# Netscale48HD_Antenna_Selector.net
KiCad netlist of a schematic drawn in Altium Designer
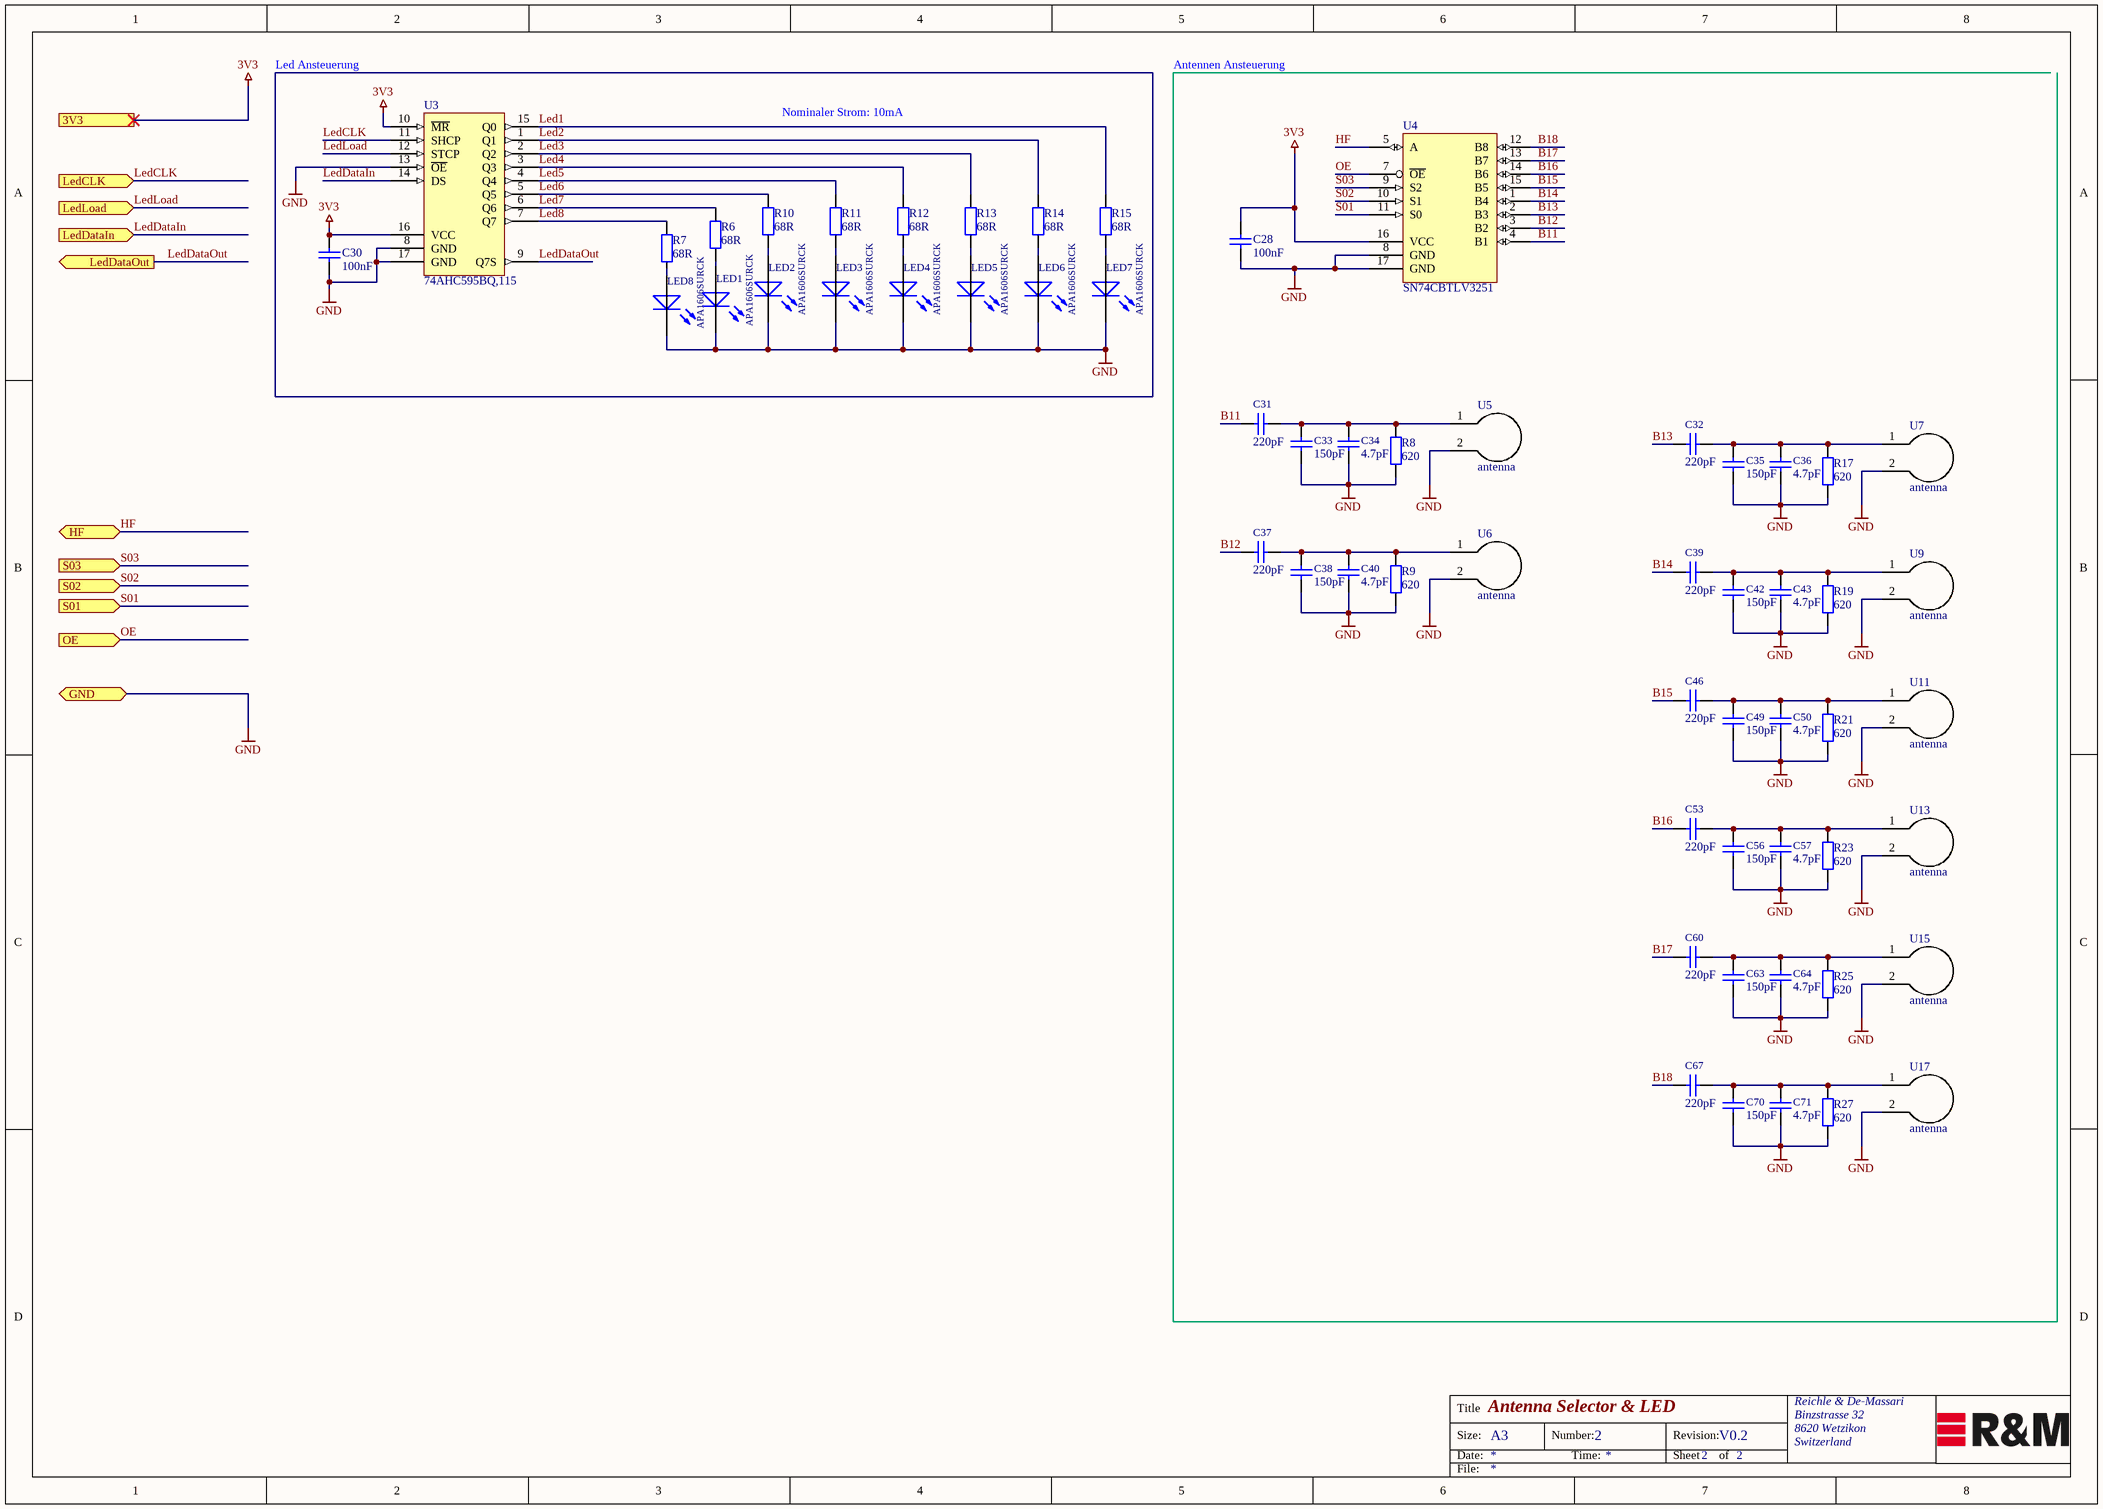
[diagram p0: Netscale48HD_Antenna_Selector.SchDoc]

(export (version "E")
  (design (tool "Eeschema 10.0.6"))
  (components
    (comp (ref "C28")
      (value "100nF")
      (footprint "CAPC1005X55N")
      (description "0.1µF ±10% 10V Ceramic Capacitor X5R 0402 (1005 Metric)")
      (fields (field (name "TOLERANCE") "Â±10%") (field (name "MANUFACTURER") "Taiyo Yuden"))
      (libsource (lib "altium-import") (part "root_1_CMP-1033-00660-1_"))
    )
    (comp (ref "C30")
      (value "100nF")
      (footprint "CAPC1005X55N")
      (description "0.1µF ±10% 10V Ceramic Capacitor X5R 0402 (1005 Metric)")
      (fields (field (name "TOLERANCE") "Â±10%") (field (name "MANUFACTURER") "Taiyo Yuden"))
      (libsource (lib "altium-import") (part "root_1_CMP-1033-00660-1_"))
    )
    (comp (ref "C31")
      (value "220pF")
      (footprint "CAPC1005X55N")
      (description "220pF ±1% 50V Ceramic Capacitor C0G, NP0 0402 (1005 Metric)")
      (fields
        (field (name "MANUFACTURER") "Murata Electronics")
        (field (name "Comment") "GCM1555C1H221FA16D")
      )
      (libsource (lib "NTB Vault") (part "706xx_R+M_InteliPhyII_KTI-00070-A.1"))
    )
    (comp (ref "C32")
      (value "220pF")
      (footprint "CAPC1005X55N")
      (description "220pF ±1% 50V Ceramic Capacitor C0G, NP0 0402 (1005 Metric)")
      (fields
        (field (name "MANUFACTURER") "Murata Electronics")
        (field (name "Comment") "GCM1555C1H221FA16D")
      )
      (libsource (lib "NTB Vault") (part "706xx_R+M_InteliPhyII_KTI-00070-A.1"))
    )
    (comp (ref "C33")
      (value "150pF")
      (footprint "CAPC1005X55N")
      (description "150pF ±1% 50V Ceramic Capacitor C0G, NP0 0402 (1005 Metric)")
      (fields
        (field (name "MANUFACTURER") "Murata Electronics North America")
        (field (name "Comment") "GRM1555C1H151FA01D")
      )
      (libsource (lib "NTB Vault") (part "706xx_R+M_InteliPhyII_KTI-00069-A.1"))
    )
    (comp (ref "C34")
      (value "4.7pF")
      (footprint "CAPC1005X55N")
      (description "4.7pF ±0.05pF 50V Ceramic Capacitor C0G, NP0 0402 (1005 Metric)")
      (fields
        (field (name "MANUFACTURER") "Murata Electronics North America")
        (field (name "Comment") "GJM1555C1H4R7WB01D")
      )
      (libsource (lib "NTB Vault") (part "706xx_R+M_InteliPhyII_KTI-00023-A.1"))
    )
    (comp (ref "C35")
      (value "150pF")
      (footprint "CAPC1005X55N")
      (description "150pF ±1% 50V Ceramic Capacitor C0G, NP0 0402 (1005 Metric)")
      (fields
        (field (name "MANUFACTURER") "Murata Electronics North America")
        (field (name "Comment") "GRM1555C1H151FA01D")
      )
      (libsource (lib "NTB Vault") (part "706xx_R+M_InteliPhyII_KTI-00069-A.1"))
    )
    (comp (ref "C36")
      (value "4.7pF")
      (footprint "CAPC1005X55N")
      (description "4.7pF ±0.05pF 50V Ceramic Capacitor C0G, NP0 0402 (1005 Metric)")
      (fields
        (field (name "MANUFACTURER") "Murata Electronics North America")
        (field (name "Comment") "GJM1555C1H4R7WB01D")
      )
      (libsource (lib "NTB Vault") (part "706xx_R+M_InteliPhyII_KTI-00023-A.1"))
    )
    (comp (ref "C37")
      (value "220pF")
      (footprint "CAPC1005X55N")
      (description "220pF ±1% 50V Ceramic Capacitor C0G, NP0 0402 (1005 Metric)")
      (fields
        (field (name "MANUFACTURER") "Murata Electronics")
        (field (name "Comment") "GCM1555C1H221FA16D")
      )
      (libsource (lib "NTB Vault") (part "706xx_R+M_InteliPhyII_KTI-00070-A.1"))
    )
    (comp (ref "C38")
      (value "150pF")
      (footprint "CAPC1005X55N")
      (description "150pF ±1% 50V Ceramic Capacitor C0G, NP0 0402 (1005 Metric)")
      (fields
        (field (name "MANUFACTURER") "Murata Electronics North America")
        (field (name "Comment") "GRM1555C1H151FA01D")
      )
      (libsource (lib "NTB Vault") (part "706xx_R+M_InteliPhyII_KTI-00069-A.1"))
    )
    (comp (ref "C39")
      (value "220pF")
      (footprint "CAPC1005X55N")
      (description "220pF ±1% 50V Ceramic Capacitor C0G, NP0 0402 (1005 Metric)")
      (fields
        (field (name "MANUFACTURER") "Murata Electronics")
        (field (name "Comment") "GCM1555C1H221FA16D")
      )
      (libsource (lib "NTB Vault") (part "706xx_R+M_InteliPhyII_KTI-00070-A.1"))
    )
    (comp (ref "C40")
      (value "4.7pF")
      (footprint "CAPC1005X55N")
      (description "4.7pF ±0.05pF 50V Ceramic Capacitor C0G, NP0 0402 (1005 Metric)")
      (fields
        (field (name "MANUFACTURER") "Murata Electronics North America")
        (field (name "Comment") "GJM1555C1H4R7WB01D")
      )
      (libsource (lib "NTB Vault") (part "706xx_R+M_InteliPhyII_KTI-00023-A.1"))
    )
    (comp (ref "C42")
      (value "150pF")
      (footprint "CAPC1005X55N")
      (description "150pF ±1% 50V Ceramic Capacitor C0G, NP0 0402 (1005 Metric)")
      (fields
        (field (name "MANUFACTURER") "Murata Electronics North America")
        (field (name "Comment") "GRM1555C1H151FA01D")
      )
      (libsource (lib "NTB Vault") (part "706xx_R+M_InteliPhyII_KTI-00069-A.1"))
    )
    (comp (ref "C43")
      (value "4.7pF")
      (footprint "CAPC1005X55N")
      (description "4.7pF ±0.05pF 50V Ceramic Capacitor C0G, NP0 0402 (1005 Metric)")
      (fields
        (field (name "MANUFACTURER") "Murata Electronics North America")
        (field (name "Comment") "GJM1555C1H4R7WB01D")
      )
      (libsource (lib "NTB Vault") (part "706xx_R+M_InteliPhyII_KTI-00023-A.1"))
    )
    (comp (ref "C46")
      (value "220pF")
      (footprint "CAPC1005X55N")
      (description "220pF ±1% 50V Ceramic Capacitor C0G, NP0 0402 (1005 Metric)")
      (fields
        (field (name "MANUFACTURER") "Murata Electronics")
        (field (name "Comment") "GCM1555C1H221FA16D")
      )
      (libsource (lib "NTB Vault") (part "706xx_R+M_InteliPhyII_KTI-00070-A.1"))
    )
    (comp (ref "C49")
      (value "150pF")
      (footprint "CAPC1005X55N")
      (description "150pF ±1% 50V Ceramic Capacitor C0G, NP0 0402 (1005 Metric)")
      (fields
        (field (name "MANUFACTURER") "Murata Electronics North America")
        (field (name "Comment") "GRM1555C1H151FA01D")
      )
      (libsource (lib "NTB Vault") (part "706xx_R+M_InteliPhyII_KTI-00069-A.1"))
    )
    (comp (ref "C50")
      (value "4.7pF")
      (footprint "CAPC1005X55N")
      (description "4.7pF ±0.05pF 50V Ceramic Capacitor C0G, NP0 0402 (1005 Metric)")
      (fields
        (field (name "MANUFACTURER") "Murata Electronics North America")
        (field (name "Comment") "GJM1555C1H4R7WB01D")
      )
      (libsource (lib "NTB Vault") (part "706xx_R+M_InteliPhyII_KTI-00023-A.1"))
    )
    (comp (ref "C53")
      (value "220pF")
      (footprint "CAPC1005X55N")
      (description "220pF ±1% 50V Ceramic Capacitor C0G, NP0 0402 (1005 Metric)")
      (fields
        (field (name "MANUFACTURER") "Murata Electronics")
        (field (name "Comment") "GCM1555C1H221FA16D")
      )
      (libsource (lib "NTB Vault") (part "706xx_R+M_InteliPhyII_KTI-00070-A.1"))
    )
    (comp (ref "C56")
      (value "150pF")
      (footprint "CAPC1005X55N")
      (description "150pF ±1% 50V Ceramic Capacitor C0G, NP0 0402 (1005 Metric)")
      (fields
        (field (name "MANUFACTURER") "Murata Electronics North America")
        (field (name "Comment") "GRM1555C1H151FA01D")
      )
      (libsource (lib "NTB Vault") (part "706xx_R+M_InteliPhyII_KTI-00069-A.1"))
    )
    (comp (ref "C57")
      (value "4.7pF")
      (footprint "CAPC1005X55N")
      (description "4.7pF ±0.05pF 50V Ceramic Capacitor C0G, NP0 0402 (1005 Metric)")
      (fields
        (field (name "MANUFACTURER") "Murata Electronics North America")
        (field (name "Comment") "GJM1555C1H4R7WB01D")
      )
      (libsource (lib "NTB Vault") (part "706xx_R+M_InteliPhyII_KTI-00023-A.1"))
    )
    (comp (ref "C60")
      (value "220pF")
      (footprint "CAPC1005X55N")
      (description "220pF ±1% 50V Ceramic Capacitor C0G, NP0 0402 (1005 Metric)")
      (fields
        (field (name "MANUFACTURER") "Murata Electronics")
        (field (name "Comment") "GCM1555C1H221FA16D")
      )
      (libsource (lib "NTB Vault") (part "706xx_R+M_InteliPhyII_KTI-00070-A.1"))
    )
    (comp (ref "C63")
      (value "150pF")
      (footprint "CAPC1005X55N")
      (description "150pF ±1% 50V Ceramic Capacitor C0G, NP0 0402 (1005 Metric)")
      (fields
        (field (name "MANUFACTURER") "Murata Electronics North America")
        (field (name "Comment") "GRM1555C1H151FA01D")
      )
      (libsource (lib "NTB Vault") (part "706xx_R+M_InteliPhyII_KTI-00069-A.1"))
    )
    (comp (ref "C64")
      (value "4.7pF")
      (footprint "CAPC1005X55N")
      (description "4.7pF ±0.05pF 50V Ceramic Capacitor C0G, NP0 0402 (1005 Metric)")
      (fields
        (field (name "MANUFACTURER") "Murata Electronics North America")
        (field (name "Comment") "GJM1555C1H4R7WB01D")
      )
      (libsource (lib "NTB Vault") (part "706xx_R+M_InteliPhyII_KTI-00023-A.1"))
    )
    (comp (ref "C67")
      (value "220pF")
      (footprint "CAPC1005X55N")
      (description "220pF ±1% 50V Ceramic Capacitor C0G, NP0 0402 (1005 Metric)")
      (fields
        (field (name "MANUFACTURER") "Murata Electronics")
        (field (name "Comment") "GCM1555C1H221FA16D")
      )
      (libsource (lib "NTB Vault") (part "706xx_R+M_InteliPhyII_KTI-00070-A.1"))
    )
    (comp (ref "C70")
      (value "150pF")
      (footprint "CAPC1005X55N")
      (description "150pF ±1% 50V Ceramic Capacitor C0G, NP0 0402 (1005 Metric)")
      (fields
        (field (name "MANUFACTURER") "Murata Electronics North America")
        (field (name "Comment") "GRM1555C1H151FA01D")
      )
      (libsource (lib "NTB Vault") (part "706xx_R+M_InteliPhyII_KTI-00069-A.1"))
    )
    (comp (ref "C71")
      (value "4.7pF")
      (footprint "CAPC1005X55N")
      (description "4.7pF ±0.05pF 50V Ceramic Capacitor C0G, NP0 0402 (1005 Metric)")
      (fields
        (field (name "MANUFACTURER") "Murata Electronics North America")
        (field (name "Comment") "GJM1555C1H4R7WB01D")
      )
      (libsource (lib "NTB Vault") (part "706xx_R+M_InteliPhyII_KTI-00023-A.1"))
    )
    (comp (ref "LED1")
      (value "APA1606SURCK")
      (footprint "Kingbright_SMD_2_RWH")
      (description "Red 630nm LED Indication - Discrete 1.95V 2-SMD, No Lead")
      (fields (field (name "MANUFACTURER") "Kingbright"))
      (libsource (lib "altium-import") (part "root_1_LED_K1_A2_"))
    )
    (comp (ref "LED2")
      (value "APA1606SURCK")
      (footprint "Kingbright_SMD_2_RWH")
      (description "Red 630nm LED Indication - Discrete 1.95V 2-SMD, No Lead")
      (fields (field (name "MANUFACTURER") "Kingbright"))
      (libsource (lib "altium-import") (part "root_1_LED_K1_A2_"))
    )
    (comp (ref "LED3")
      (value "APA1606SURCK")
      (footprint "Kingbright_SMD_2_RWH")
      (description "Red 630nm LED Indication - Discrete 1.95V 2-SMD, No Lead")
      (fields (field (name "MANUFACTURER") "Kingbright"))
      (libsource (lib "altium-import") (part "root_1_LED_K1_A2_"))
    )
    (comp (ref "LED4")
      (value "APA1606SURCK")
      (footprint "Kingbright_SMD_2_RWH")
      (description "Red 630nm LED Indication - Discrete 1.95V 2-SMD, No Lead")
      (fields (field (name "MANUFACTURER") "Kingbright"))
      (libsource (lib "altium-import") (part "root_1_LED_K1_A2_"))
    )
    (comp (ref "LED5")
      (value "APA1606SURCK")
      (footprint "Kingbright_SMD_2_RWH")
      (description "Red 630nm LED Indication - Discrete 1.95V 2-SMD, No Lead")
      (fields (field (name "MANUFACTURER") "Kingbright"))
      (libsource (lib "altium-import") (part "root_1_LED_K1_A2_"))
    )
    (comp (ref "LED6")
      (value "APA1606SURCK")
      (footprint "Kingbright_SMD_2_RWH")
      (description "Red 630nm LED Indication - Discrete 1.95V 2-SMD, No Lead")
      (fields (field (name "MANUFACTURER") "Kingbright"))
      (libsource (lib "altium-import") (part "root_1_LED_K1_A2_"))
    )
    (comp (ref "LED7")
      (value "APA1606SURCK")
      (footprint "Kingbright_SMD_2_RWH")
      (description "Red 630nm LED Indication - Discrete 1.95V 2-SMD, No Lead")
      (fields (field (name "MANUFACTURER") "Kingbright"))
      (libsource (lib "altium-import") (part "root_1_LED_K1_A2_"))
    )
    (comp (ref "LED8")
      (value "APA1606SURCK")
      (footprint "Kingbright_SMD_2_RWH")
      (description "Red 630nm LED Indication - Discrete 1.95V 2-SMD, No Lead")
      (fields (field (name "MANUFACTURER") "Kingbright"))
      (libsource (lib "altium-import") (part "root_1_LED_K1_A2_"))
    )
    (comp (ref "R6")
      (value "68R")
      (footprint "RESC1005X40N")
      (description "68 Ohms ±1% 0.125W, 1/8W Chip Resistor 0402 (1005 Metric) Pulse Withstanding Thick Film")
      (fields
        (field (name "MANUFACTURER") "TE Connectivity Passive Product")
        (field (name "Comment") "CRGP0402F68R")
      )
      (libsource (lib "") (part "PassResBas0201-00055-A.2_1"))
    )
    (comp (ref "R7")
      (value "68R")
      (footprint "RESC1005X40N")
      (description "68 Ohms ±1% 0.125W, 1/8W Chip Resistor 0402 (1005 Metric) Pulse Withstanding Thick Film")
      (fields
        (field (name "MANUFACTURER") "TE Connectivity Passive Product")
        (field (name "Comment") "CRGP0402F68R")
      )
      (libsource (lib "") (part "PassResBas0201-00055-A.2_1"))
    )
    (comp (ref "R8")
      (value "620")
      (footprint "RESC1005X40N")
      (description "620 Ohms ±1% 0.1W, 1/10W Chip Resistor 0402 (1005 Metric) Automotive AEC-Q200 Thick Film")
      (fields
        (field (name "MANUFACTURER") "Panasonic Electronic Components")
        (field (name "Comment") "ERJ-2RKF6200X")
      )
      (libsource (lib "RDM_Altium_Library") (part "PassResBas0201-00055-A.2"))
    )
    (comp (ref "R9")
      (value "620")
      (footprint "RESC1005X40N")
      (description "620 Ohms ±1% 0.1W, 1/10W Chip Resistor 0402 (1005 Metric) Automotive AEC-Q200 Thick Film")
      (fields
        (field (name "MANUFACTURER") "Panasonic Electronic Components")
        (field (name "Comment") "ERJ-2RKF6200X")
      )
      (libsource (lib "RDM_Altium_Library") (part "PassResBas0201-00055-A.2"))
    )
    (comp (ref "R10")
      (value "68R")
      (footprint "RESC1005X40N")
      (description "68 Ohms ±1% 0.125W, 1/8W Chip Resistor 0402 (1005 Metric) Pulse Withstanding Thick Film")
      (fields
        (field (name "MANUFACTURER") "TE Connectivity Passive Product")
        (field (name "Comment") "CRGP0402F68R")
      )
      (libsource (lib "") (part "PassResBas0201-00055-A.2_1"))
    )
    (comp (ref "R11")
      (value "68R")
      (footprint "RESC1005X40N")
      (description "68 Ohms ±1% 0.125W, 1/8W Chip Resistor 0402 (1005 Metric) Pulse Withstanding Thick Film")
      (fields
        (field (name "MANUFACTURER") "TE Connectivity Passive Product")
        (field (name "Comment") "CRGP0402F68R")
      )
      (libsource (lib "") (part "PassResBas0201-00055-A.2_1"))
    )
    (comp (ref "R12")
      (value "68R")
      (footprint "RESC1005X40N")
      (description "68 Ohms ±1% 0.125W, 1/8W Chip Resistor 0402 (1005 Metric) Pulse Withstanding Thick Film")
      (fields
        (field (name "MANUFACTURER") "TE Connectivity Passive Product")
        (field (name "Comment") "CRGP0402F68R")
      )
      (libsource (lib "") (part "PassResBas0201-00055-A.2_1"))
    )
    (comp (ref "R13")
      (value "68R")
      (footprint "RESC1005X40N")
      (description "68 Ohms ±1% 0.125W, 1/8W Chip Resistor 0402 (1005 Metric) Pulse Withstanding Thick Film")
      (fields
        (field (name "MANUFACTURER") "TE Connectivity Passive Product")
        (field (name "Comment") "CRGP0402F68R")
      )
      (libsource (lib "") (part "PassResBas0201-00055-A.2_1"))
    )
    (comp (ref "R14")
      (value "68R")
      (footprint "RESC1005X40N")
      (description "68 Ohms ±1% 0.125W, 1/8W Chip Resistor 0402 (1005 Metric) Pulse Withstanding Thick Film")
      (fields
        (field (name "MANUFACTURER") "TE Connectivity Passive Product")
        (field (name "Comment") "CRGP0402F68R")
      )
      (libsource (lib "") (part "PassResBas0201-00055-A.2_1"))
    )
    (comp (ref "R15")
      (value "68R")
      (footprint "RESC1005X40N")
      (description "68 Ohms ±1% 0.125W, 1/8W Chip Resistor 0402 (1005 Metric) Pulse Withstanding Thick Film")
      (fields
        (field (name "MANUFACTURER") "TE Connectivity Passive Product")
        (field (name "Comment") "CRGP0402F68R")
      )
      (libsource (lib "") (part "PassResBas0201-00055-A.2_1"))
    )
    (comp (ref "R17")
      (value "620")
      (footprint "RESC1005X40N")
      (description "620 Ohms ±1% 0.1W, 1/10W Chip Resistor 0402 (1005 Metric) Automotive AEC-Q200 Thick Film")
      (fields
        (field (name "MANUFACTURER") "Panasonic Electronic Components")
        (field (name "Comment") "ERJ-2RKF6200X")
      )
      (libsource (lib "RDM_Altium_Library") (part "PassResBas0201-00055-A.2"))
    )
    (comp (ref "R19")
      (value "620")
      (footprint "RESC1005X40N")
      (description "620 Ohms ±1% 0.1W, 1/10W Chip Resistor 0402 (1005 Metric) Automotive AEC-Q200 Thick Film")
      (fields
        (field (name "MANUFACTURER") "Panasonic Electronic Components")
        (field (name "Comment") "ERJ-2RKF6200X")
      )
      (libsource (lib "RDM_Altium_Library") (part "PassResBas0201-00055-A.2"))
    )
    (comp (ref "R21")
      (value "620")
      (footprint "RESC1005X40N")
      (description "620 Ohms ±1% 0.1W, 1/10W Chip Resistor 0402 (1005 Metric) Automotive AEC-Q200 Thick Film")
      (fields
        (field (name "MANUFACTURER") "Panasonic Electronic Components")
        (field (name "Comment") "ERJ-2RKF6200X")
      )
      (libsource (lib "RDM_Altium_Library") (part "PassResBas0201-00055-A.2"))
    )
    (comp (ref "R23")
      (value "620")
      (footprint "RESC1005X40N")
      (description "620 Ohms ±1% 0.1W, 1/10W Chip Resistor 0402 (1005 Metric) Automotive AEC-Q200 Thick Film")
      (fields
        (field (name "MANUFACTURER") "Panasonic Electronic Components")
        (field (name "Comment") "ERJ-2RKF6200X")
      )
      (libsource (lib "RDM_Altium_Library") (part "PassResBas0201-00055-A.2"))
    )
    (comp (ref "R25")
      (value "620")
      (footprint "RESC1005X40N")
      (description "620 Ohms ±1% 0.1W, 1/10W Chip Resistor 0402 (1005 Metric) Automotive AEC-Q200 Thick Film")
      (fields
        (field (name "MANUFACTURER") "Panasonic Electronic Components")
        (field (name "Comment") "ERJ-2RKF6200X")
      )
      (libsource (lib "RDM_Altium_Library") (part "PassResBas0201-00055-A.2"))
    )
    (comp (ref "R27")
      (value "620")
      (footprint "RESC1005X40N")
      (description "620 Ohms ±1% 0.1W, 1/10W Chip Resistor 0402 (1005 Metric) Automotive AEC-Q200 Thick Film")
      (fields
        (field (name "MANUFACTURER") "Panasonic Electronic Components")
        (field (name "Comment") "ERJ-2RKF6200X")
      )
      (libsource (lib "RDM_Altium_Library") (part "PassResBas0201-00055-A.2"))
    )
    (comp (ref "U3")
      (value "74AHC595BQ,115")
      (footprint "NexperiaUSAInc_16-VFQFN_16_R")
      (description "IC 8BIT SHIFT REGISTER 16HVQFN")
      (fields (field (name "MANUFACTURER") "Nexperia USA Inc."))
      (libsource (lib "RDM_Altium_Library") (part "NexperiaUSAInc_74AHC595,115_16-VFQFN_16"))
    )
    (comp (ref "U4")
      (value "SN74CBTLV3251")
      (footprint "TexasInstruments_16-VFQFN_16_R")
      (description "Multiplexer Switch ICs Sngl-Pole Dbl-Throw Analog Switch")
      (fields (field (name "MANUFACTURER") "Texas Instruments"))
      (libsource (lib "RDM_Altium_Library") (part "SN74CBTLV3251RGYR"))
    )
    (comp (ref "U5")
      (value "antenna")
      (footprint "antenna_1_layer")
      (libsource (lib "RDM_Altium_Library") (part "antenna"))
    )
    (comp (ref "U6")
      (value "antenna")
      (footprint "antenna_1_layer")
      (libsource (lib "RDM_Altium_Library") (part "antenna"))
    )
    (comp (ref "U7")
      (value "antenna")
      (footprint "antenna_1_layer")
      (libsource (lib "RDM_Altium_Library") (part "antenna"))
    )
    (comp (ref "U9")
      (value "antenna")
      (footprint "antenna_1_layer")
      (libsource (lib "RDM_Altium_Library") (part "antenna"))
    )
    (comp (ref "U11")
      (value "antenna")
      (footprint "antenna_1_layer")
      (libsource (lib "RDM_Altium_Library") (part "antenna"))
    )
    (comp (ref "U13")
      (value "antenna")
      (footprint "antenna_1_layer")
      (libsource (lib "RDM_Altium_Library") (part "antenna"))
    )
    (comp (ref "U15")
      (value "antenna")
      (footprint "antenna_1_layer")
      (libsource (lib "RDM_Altium_Library") (part "antenna"))
    )
    (comp (ref "U17")
      (value "antenna")
      (footprint "antenna_1_layer")
      (libsource (lib "RDM_Altium_Library") (part "antenna"))
    )
  )
  (nets
    (net (code "1") (name "/B11") (class "Default")
      (node (ref "C31") (pin "1") (pinfunction "Pos_1") (pintype "passive"))
      (node (ref "U4") (pin "4") (pinfunction "B1_4") (pintype "bidirectional"))
    )
    (net (code "2") (name "/B12") (class "Default")
      (node (ref "C37") (pin "1") (pinfunction "Pos_1") (pintype "passive"))
      (node (ref "U4") (pin "3") (pinfunction "B2_3") (pintype "bidirectional"))
    )
    (net (code "3") (name "/B13") (class "Default")
      (node (ref "C32") (pin "1") (pinfunction "Pos_1") (pintype "passive"))
      (node (ref "U4") (pin "2") (pinfunction "B3_2") (pintype "bidirectional"))
    )
    (net (code "4") (name "/B14") (class "Default")
      (node (ref "C39") (pin "1") (pinfunction "Pos_1") (pintype "passive"))
      (node (ref "U4") (pin "1") (pinfunction "B4_1") (pintype "bidirectional"))
    )
    (net (code "5") (name "/B15") (class "Default")
      (node (ref "C46") (pin "1") (pinfunction "Pos_1") (pintype "passive"))
      (node (ref "U4") (pin "15") (pinfunction "B5_15") (pintype "bidirectional"))
    )
    (net (code "6") (name "/B16") (class "Default")
      (node (ref "C53") (pin "1") (pinfunction "Pos_1") (pintype "passive"))
      (node (ref "U4") (pin "14") (pinfunction "B6_14") (pintype "bidirectional"))
    )
    (net (code "7") (name "/B17") (class "Default")
      (node (ref "C60") (pin "1") (pinfunction "Pos_1") (pintype "passive"))
      (node (ref "U4") (pin "13") (pinfunction "B7_13") (pintype "bidirectional"))
    )
    (net (code "8") (name "/B18") (class "Default")
      (node (ref "C67") (pin "1") (pinfunction "Pos_1") (pintype "passive"))
      (node (ref "U4") (pin "12") (pinfunction "B8_12") (pintype "bidirectional"))
    )
    (net (code "9") (name "/HF") (class "Default")
      (node (ref "U4") (pin "5") (pinfunction "A_5") (pintype "bidirectional"))
    )
    (net (code "10") (name "/Led1") (class "Default")
      (node (ref "R15") (pin "1") (pinfunction "1_1") (pintype "passive"))
      (node (ref "U3") (pin "15") (pinfunction "Q0_15") (pintype "output"))
    )
    (net (code "11") (name "/Led2") (class "Default")
      (node (ref "R14") (pin "1") (pinfunction "1_1") (pintype "passive"))
      (node (ref "U3") (pin "1") (pinfunction "Q1_1") (pintype "output"))
    )
    (net (code "12") (name "/Led3") (class "Default")
      (node (ref "R13") (pin "1") (pinfunction "1_1") (pintype "passive"))
      (node (ref "U3") (pin "2") (pinfunction "Q2_2") (pintype "output"))
    )
    (net (code "13") (name "/Led4") (class "Default")
      (node (ref "R12") (pin "1") (pinfunction "1_1") (pintype "passive"))
      (node (ref "U3") (pin "3") (pinfunction "Q3_3") (pintype "output"))
    )
    (net (code "14") (name "/Led5") (class "Default")
      (node (ref "R11") (pin "1") (pinfunction "1_1") (pintype "passive"))
      (node (ref "U3") (pin "4") (pinfunction "Q4_4") (pintype "output"))
    )
    (net (code "15") (name "/Led6") (class "Default")
      (node (ref "R10") (pin "1") (pinfunction "1_1") (pintype "passive"))
      (node (ref "U3") (pin "5") (pinfunction "Q5_5") (pintype "output"))
    )
    (net (code "16") (name "/Led7") (class "Default")
      (node (ref "R6") (pin "1") (pinfunction "1_1") (pintype "passive"))
      (node (ref "U3") (pin "6") (pinfunction "Q6_6") (pintype "output"))
    )
    (net (code "17") (name "/Led8") (class "Default")
      (node (ref "R7") (pin "1") (pinfunction "1_1") (pintype "passive"))
      (node (ref "U3") (pin "7") (pinfunction "Q7_7") (pintype "output"))
    )
    (net (code "18") (name "/LedCLK") (class "Default")
      (node (ref "U3") (pin "11") (pinfunction "SHCP_11") (pintype "input"))
    )
    (net (code "19") (name "/LedDataIn") (class "Default")
      (node (ref "U3") (pin "14") (pinfunction "DS_14") (pintype "input"))
    )
    (net (code "20") (name "/LedDataOut") (class "Default")
      (node (ref "U3") (pin "9") (pinfunction "Q7S_9") (pintype "output"))
    )
    (net (code "21") (name "/LedLoad") (class "Default")
      (node (ref "U3") (pin "12") (pinfunction "STCP_12") (pintype "input"))
    )
    (net (code "22") (name "/OE") (class "Default")
      (node (ref "U4") (pin "7") (pinfunction "~{OE}_7") (pintype "passive"))
    )
    (net (code "23") (name "/S01") (class "Default")
      (node (ref "U4") (pin "11") (pinfunction "S0_11") (pintype "input"))
    )
    (net (code "24") (name "/S02") (class "Default")
      (node (ref "U4") (pin "10") (pinfunction "S1_10") (pintype "input"))
    )
    (net (code "25") (name "/S03") (class "Default")
      (node (ref "U4") (pin "9") (pinfunction "S2_9") (pintype "input"))
    )
    (net (code "26") (name "3V3") (class "Default")
      (node (ref "C28") (pin "2") (pinfunction "2_2") (pintype "passive"))
      (node (ref "C30") (pin "2") (pinfunction "2_2") (pintype "passive"))
      (node (ref "U3") (pin "10") (pinfunction "~{MR}_10") (pintype "input"))
      (node (ref "U3") (pin "16") (pinfunction "VCC_16") (pintype "power_in"))
      (node (ref "U4") (pin "16") (pinfunction "VCC_16") (pintype "power_in"))
    )
    (net (code "27") (name "GND") (class "Default")
      (node (ref "C28") (pin "1") (pinfunction "1_1") (pintype "passive"))
      (node (ref "C30") (pin "1") (pinfunction "1_1") (pintype "passive"))
      (node (ref "C33") (pin "1") (pinfunction "Pos_1") (pintype "passive"))
      (node (ref "C34") (pin "1") (pinfunction "Pos_1") (pintype "passive"))
      (node (ref "C35") (pin "1") (pinfunction "Pos_1") (pintype "passive"))
      (node (ref "C36") (pin "1") (pinfunction "Pos_1") (pintype "passive"))
      (node (ref "C38") (pin "1") (pinfunction "Pos_1") (pintype "passive"))
      (node (ref "C40") (pin "1") (pinfunction "Pos_1") (pintype "passive"))
      (node (ref "C42") (pin "1") (pinfunction "Pos_1") (pintype "passive"))
      (node (ref "C43") (pin "1") (pinfunction "Pos_1") (pintype "passive"))
      (node (ref "C49") (pin "1") (pinfunction "Pos_1") (pintype "passive"))
      (node (ref "C50") (pin "1") (pinfunction "Pos_1") (pintype "passive"))
      (node (ref "C56") (pin "1") (pinfunction "Pos_1") (pintype "passive"))
      (node (ref "C57") (pin "1") (pinfunction "Pos_1") (pintype "passive"))
      (node (ref "C63") (pin "1") (pinfunction "Pos_1") (pintype "passive"))
      (node (ref "C64") (pin "1") (pinfunction "Pos_1") (pintype "passive"))
      (node (ref "C70") (pin "1") (pinfunction "Pos_1") (pintype "passive"))
      (node (ref "C71") (pin "1") (pinfunction "Pos_1") (pintype "passive"))
      (node (ref "LED1") (pin "1") (pinfunction "K_1") (pintype "passive"))
      (node (ref "LED2") (pin "1") (pinfunction "K_1") (pintype "passive"))
      (node (ref "LED3") (pin "1") (pinfunction "K_1") (pintype "passive"))
      (node (ref "LED4") (pin "1") (pinfunction "K_1") (pintype "passive"))
      (node (ref "LED5") (pin "1") (pinfunction "K_1") (pintype "passive"))
      (node (ref "LED6") (pin "1") (pinfunction "K_1") (pintype "passive"))
      (node (ref "LED7") (pin "1") (pinfunction "K_1") (pintype "passive"))
      (node (ref "LED8") (pin "1") (pinfunction "K_1") (pintype "passive"))
      (node (ref "R17") (pin "1") (pinfunction "1_1") (pintype "passive"))
      (node (ref "R19") (pin "1") (pinfunction "1_1") (pintype "passive"))
      (node (ref "R21") (pin "1") (pinfunction "1_1") (pintype "passive"))
      (node (ref "R23") (pin "1") (pinfunction "1_1") (pintype "passive"))
      (node (ref "R25") (pin "1") (pinfunction "1_1") (pintype "passive"))
      (node (ref "R27") (pin "1") (pinfunction "1_1") (pintype "passive"))
      (node (ref "R8") (pin "1") (pinfunction "1_1") (pintype "passive"))
      (node (ref "R9") (pin "1") (pinfunction "1_1") (pintype "passive"))
      (node (ref "U11") (pin "2") (pinfunction "2_2") (pintype "passive"))
      (node (ref "U13") (pin "2") (pinfunction "2_2") (pintype "passive"))
      (node (ref "U15") (pin "2") (pinfunction "2_2") (pintype "passive"))
      (node (ref "U17") (pin "2") (pinfunction "2_2") (pintype "passive"))
      (node (ref "U3") (pin "13") (pinfunction "~{OE}_13") (pintype "input"))
      (node (ref "U3") (pin "17") (pinfunction "GND_17") (pintype "passive"))
      (node (ref "U3") (pin "8") (pinfunction "GND_8") (pintype "passive"))
      (node (ref "U4") (pin "17") (pinfunction "GND_17") (pintype "passive"))
      (node (ref "U4") (pin "8") (pinfunction "GND_8") (pintype "passive"))
      (node (ref "U5") (pin "2") (pinfunction "2_2") (pintype "passive"))
      (node (ref "U6") (pin "2") (pinfunction "2_2") (pintype "passive"))
      (node (ref "U7") (pin "2") (pinfunction "2_2") (pintype "passive"))
      (node (ref "U9") (pin "2") (pinfunction "2_2") (pintype "passive"))
    )
    (net (code "28") (name "Net-(C31-Neg)") (class "Default")
      (node (ref "C31") (pin "2") (pinfunction "Neg_2") (pintype "passive"))
      (node (ref "C33") (pin "2") (pinfunction "Neg_2") (pintype "passive"))
      (node (ref "C34") (pin "2") (pinfunction "Neg_2") (pintype "passive"))
      (node (ref "R8") (pin "2") (pinfunction "2_2") (pintype "passive"))
      (node (ref "U5") (pin "1") (pinfunction "1_1") (pintype "passive"))
    )
    (net (code "29") (name "Net-(C32-Neg)") (class "Default")
      (node (ref "C32") (pin "2") (pinfunction "Neg_2") (pintype "passive"))
      (node (ref "C35") (pin "2") (pinfunction "Neg_2") (pintype "passive"))
      (node (ref "C36") (pin "2") (pinfunction "Neg_2") (pintype "passive"))
      (node (ref "R17") (pin "2") (pinfunction "2_2") (pintype "passive"))
      (node (ref "U7") (pin "1") (pinfunction "1_1") (pintype "passive"))
    )
    (net (code "30") (name "Net-(C37-Neg)") (class "Default")
      (node (ref "C37") (pin "2") (pinfunction "Neg_2") (pintype "passive"))
      (node (ref "C38") (pin "2") (pinfunction "Neg_2") (pintype "passive"))
      (node (ref "C40") (pin "2") (pinfunction "Neg_2") (pintype "passive"))
      (node (ref "R9") (pin "2") (pinfunction "2_2") (pintype "passive"))
      (node (ref "U6") (pin "1") (pinfunction "1_1") (pintype "passive"))
    )
    (net (code "31") (name "Net-(C39-Neg)") (class "Default")
      (node (ref "C39") (pin "2") (pinfunction "Neg_2") (pintype "passive"))
      (node (ref "C42") (pin "2") (pinfunction "Neg_2") (pintype "passive"))
      (node (ref "C43") (pin "2") (pinfunction "Neg_2") (pintype "passive"))
      (node (ref "R19") (pin "2") (pinfunction "2_2") (pintype "passive"))
      (node (ref "U9") (pin "1") (pinfunction "1_1") (pintype "passive"))
    )
    (net (code "32") (name "Net-(C46-Neg)") (class "Default")
      (node (ref "C46") (pin "2") (pinfunction "Neg_2") (pintype "passive"))
      (node (ref "C49") (pin "2") (pinfunction "Neg_2") (pintype "passive"))
      (node (ref "C50") (pin "2") (pinfunction "Neg_2") (pintype "passive"))
      (node (ref "R21") (pin "2") (pinfunction "2_2") (pintype "passive"))
      (node (ref "U11") (pin "1") (pinfunction "1_1") (pintype "passive"))
    )
    (net (code "33") (name "Net-(C53-Neg)") (class "Default")
      (node (ref "C53") (pin "2") (pinfunction "Neg_2") (pintype "passive"))
      (node (ref "C56") (pin "2") (pinfunction "Neg_2") (pintype "passive"))
      (node (ref "C57") (pin "2") (pinfunction "Neg_2") (pintype "passive"))
      (node (ref "R23") (pin "2") (pinfunction "2_2") (pintype "passive"))
      (node (ref "U13") (pin "1") (pinfunction "1_1") (pintype "passive"))
    )
    (net (code "34") (name "Net-(C60-Neg)") (class "Default")
      (node (ref "C60") (pin "2") (pinfunction "Neg_2") (pintype "passive"))
      (node (ref "C63") (pin "2") (pinfunction "Neg_2") (pintype "passive"))
      (node (ref "C64") (pin "2") (pinfunction "Neg_2") (pintype "passive"))
      (node (ref "R25") (pin "2") (pinfunction "2_2") (pintype "passive"))
      (node (ref "U15") (pin "1") (pinfunction "1_1") (pintype "passive"))
    )
    (net (code "35") (name "Net-(C67-Neg)") (class "Default")
      (node (ref "C67") (pin "2") (pinfunction "Neg_2") (pintype "passive"))
      (node (ref "C70") (pin "2") (pinfunction "Neg_2") (pintype "passive"))
      (node (ref "C71") (pin "2") (pinfunction "Neg_2") (pintype "passive"))
      (node (ref "R27") (pin "2") (pinfunction "2_2") (pintype "passive"))
      (node (ref "U17") (pin "1") (pinfunction "1_1") (pintype "passive"))
    )
    (net (code "36") (name "Net-(LED1-A)") (class "Default")
      (node (ref "LED1") (pin "2") (pinfunction "A_2") (pintype "passive"))
      (node (ref "R6") (pin "2") (pinfunction "2_2") (pintype "passive"))
    )
    (net (code "37") (name "Net-(LED2-A)") (class "Default")
      (node (ref "LED2") (pin "2") (pinfunction "A_2") (pintype "passive"))
      (node (ref "R10") (pin "2") (pinfunction "2_2") (pintype "passive"))
    )
    (net (code "38") (name "Net-(LED3-A)") (class "Default")
      (node (ref "LED3") (pin "2") (pinfunction "A_2") (pintype "passive"))
      (node (ref "R11") (pin "2") (pinfunction "2_2") (pintype "passive"))
    )
    (net (code "39") (name "Net-(LED4-A)") (class "Default")
      (node (ref "LED4") (pin "2") (pinfunction "A_2") (pintype "passive"))
      (node (ref "R12") (pin "2") (pinfunction "2_2") (pintype "passive"))
    )
    (net (code "40") (name "Net-(LED5-A)") (class "Default")
      (node (ref "LED5") (pin "2") (pinfunction "A_2") (pintype "passive"))
      (node (ref "R13") (pin "2") (pinfunction "2_2") (pintype "passive"))
    )
    (net (code "41") (name "Net-(LED6-A)") (class "Default")
      (node (ref "LED6") (pin "2") (pinfunction "A_2") (pintype "passive"))
      (node (ref "R14") (pin "2") (pinfunction "2_2") (pintype "passive"))
    )
    (net (code "42") (name "Net-(LED7-A)") (class "Default")
      (node (ref "LED7") (pin "2") (pinfunction "A_2") (pintype "passive"))
      (node (ref "R15") (pin "2") (pinfunction "2_2") (pintype "passive"))
    )
    (net (code "43") (name "Net-(LED8-A)") (class "Default")
      (node (ref "LED8") (pin "2") (pinfunction "A_2") (pintype "passive"))
      (node (ref "R7") (pin "2") (pinfunction "2_2") (pintype "passive"))
    )
  )
)
